# ADCs.net
KiCad netlist of a schematic drawn in Altium Designer
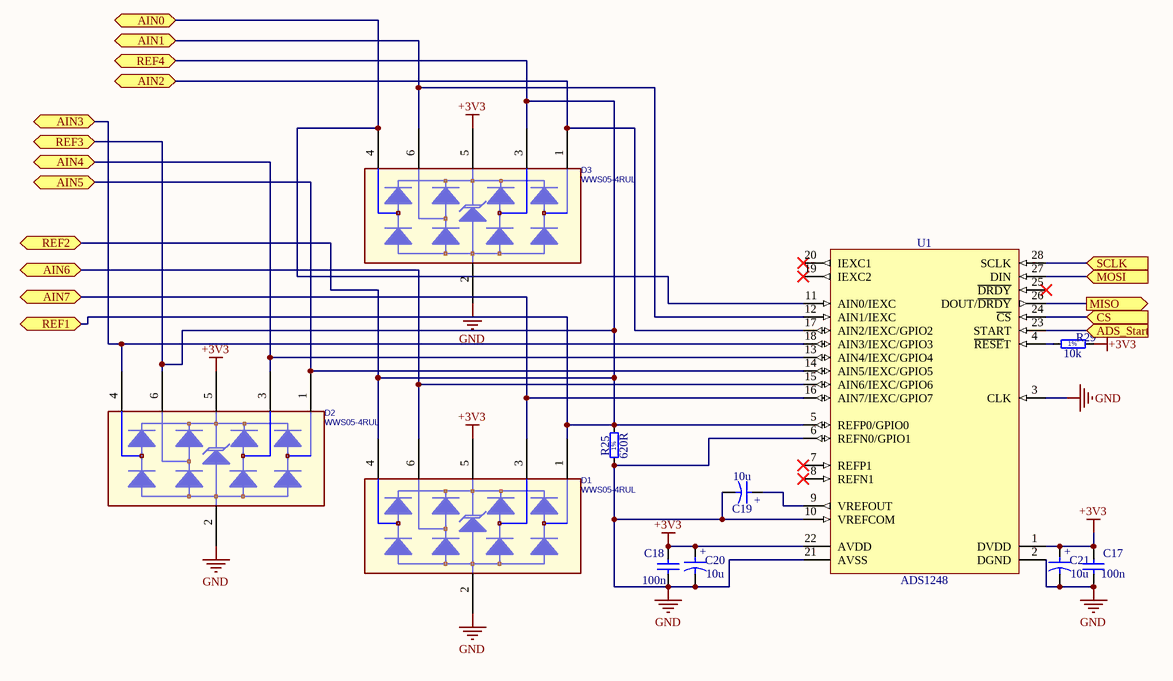
[diagram p0: ADCs.SchDoc]

(export (version "E")
  (design (tool "Eeschema 10.0.6"))
  (components
    (comp (ref "C17")
      (value "100n")
      (footprint "CAPC1005X55N")
      (description "Non-polarised capacitor")
      (fields
        (field (name "PART NUMBER") "CC0402_100NF_16V_10%_X7R")
        (field (name "VOLTAGE") "16V")
        (field (name "AUTHOR") "CERN DEM JLC")
      )
      (libsource (lib "Capacitors") (part "Capacitor - non polarized"))
    )
    (comp (ref "C18")
      (value "100n")
      (footprint "CAPC1005X55N")
      (description "Non-polarised capacitor")
      (fields
        (field (name "PART NUMBER") "CC0402_100NF_16V_10%_X7R")
        (field (name "VOLTAGE") "16V")
        (field (name "AUTHOR") "CERN DEM JLC")
      )
      (libsource (lib "Capacitors") (part "Capacitor - non polarized"))
    )
    (comp (ref "C19")
      (value "10u")
      (footprint "CAPMP3216X180N")
      (description "Polarised capacitor")
      (fields
        (field (name "PART NUMBER") "CTE7343-31_10UF_25V_10%")
        (field (name "VOLTAGE") "25V")
        (field (name "AUTHOR") "CERN DEM JMW")
      )
      (libsource (lib "Capacitors") (part "Capacitor - polarized"))
    )
    (comp (ref "C20")
      (value "10u")
      (footprint "CAPMP3216X180N")
      (description "Polarised capacitor")
      (fields
        (field (name "PART NUMBER") "CTE7343-31_10UF_25V_10%")
        (field (name "VOLTAGE") "25V")
        (field (name "AUTHOR") "CERN DEM JMW")
      )
      (libsource (lib "Capacitors") (part "Capacitor - polarized"))
    )
    (comp (ref "C21")
      (value "10u")
      (footprint "CAPMP3216X180N")
      (description "Polarised capacitor")
      (fields
        (field (name "PART NUMBER") "CTE7343-31_10UF_25V_10%")
        (field (name "VOLTAGE") "25V")
        (field (name "AUTHOR") "CERN DEM JMW")
      )
      (libsource (lib "Capacitors") (part "Capacitor - polarized"))
    )
    (comp (ref "D1")
      (value "WWS05-4RUL")
      (description "DIODE,RCLAMP0524P,SEMTECH")
      (libsource (lib "LIBRARY_SCH") (part "D_TVS_WWS05-4RUL"))
    )
    (comp (ref "D2")
      (value "WWS05-4RUL")
      (description "DIODE,RCLAMP0524P,SEMTECH")
      (libsource (lib "LIBRARY_SCH") (part "D_TVS_WWS05-4RUL"))
    )
    (comp (ref "D3")
      (value "WWS05-4RUL")
      (description "DIODE,RCLAMP0524P,SEMTECH")
      (libsource (lib "LIBRARY_SCH") (part "D_TVS_WWS05-4RUL"))
    )
    (comp (ref "R25")
      (value "620R")
      (footprint "RESC1005X40N")
      (description "Resistor - 1%")
      (fields
        (field (name "PART NUMBER") "R0402_620R_1%_0.0625W_100PPM")
        (field (name "POWER") "0.0625W")
        (field (name "AUTHOR") "CERN DEM JLC")
      )
      (libsource (lib "Resistors") (part "Resistor - 1%"))
    )
    (comp (ref "R29")
      (value "10k")
      (footprint "RESC1005X40N")
      (description "Resistor - 1%")
      (fields
        (field (name "PART NUMBER") "R0402_10K_1%_0.0625W_100PPM")
        (field (name "POWER") "0.0625W")
        (field (name "AUTHOR") "CERN DEM JLC")
      )
      (libsource (lib "Resistors") (part "Resistor - 1%"))
    )
    (comp (ref "U1")
      (value "ADS1248")
      (footprint "SOP65P640X120-28N")
      (description "24-Bit Analog-to-Digital Converter for Temperature Sensors")
      (fields
        (field (name "PART NUMBER") "ADS1248IPWR")
        (field (name "MANUFACTURER") "TEXAS INSTRUMENTS")
        (field (name "AUTHOR") "CERN DEM JLC")
      )
      (libsource (lib "ICs And Semiconductors") (part "ADS1248"))
    )
  )
  (nets
    (net (code "1") (name "+3V3") (class "Default")
      (node (ref "C17") (pin "2") (pinfunction "2_2") (pintype "passive"))
      (node (ref "C18") (pin "2") (pinfunction "2_2") (pintype "passive"))
      (node (ref "C20") (pin "1") (pinfunction "1_1") (pintype "passive"))
      (node (ref "C21") (pin "1") (pinfunction "1_1") (pintype "passive"))
      (node (ref "D1") (pin "5") (pinfunction "5_5") (pintype "passive"))
      (node (ref "D2") (pin "5") (pinfunction "5_5") (pintype "passive"))
      (node (ref "D3") (pin "5") (pinfunction "5_5") (pintype "passive"))
      (node (ref "R29") (pin "2") (pinfunction "2_2") (pintype "passive"))
      (node (ref "U1") (pin "1") (pinfunction "DVDD_1") (pintype "power_in"))
      (node (ref "U1") (pin "22") (pinfunction "AVDD_22") (pintype "power_in"))
    )
    (net (code "2") (name "/ADS_Start") (class "Default")
      (node (ref "U1") (pin "23") (pinfunction "START_23") (pintype "input"))
    )
    (net (code "3") (name "/AIN0") (class "Default")
      (node (ref "D3") (pin "4") (pinfunction "4_4") (pintype "passive"))
      (node (ref "U1") (pin "11") (pinfunction "AIN0/IEXC_11") (pintype "input"))
    )
    (net (code "4") (name "/AIN1") (class "Default")
      (node (ref "D3") (pin "6") (pinfunction "6_6") (pintype "passive"))
      (node (ref "U1") (pin "12") (pinfunction "AIN1/IEXC_12") (pintype "input"))
    )
    (net (code "5") (name "/AIN2") (class "Default")
      (node (ref "D3") (pin "1") (pinfunction "1_1") (pintype "passive"))
      (node (ref "U1") (pin "17") (pinfunction "AIN2/IEXC/GPIO2_17") (pintype "bidirectional"))
    )
    (net (code "6") (name "/AIN3") (class "Default")
      (node (ref "D2") (pin "4") (pinfunction "4_4") (pintype "passive"))
      (node (ref "U1") (pin "18") (pinfunction "AIN3/IEXC/GPIO3_18") (pintype "bidirectional"))
    )
    (net (code "7") (name "/AIN4") (class "Default")
      (node (ref "D2") (pin "3") (pinfunction "3_3") (pintype "passive"))
      (node (ref "U1") (pin "13") (pinfunction "AIN4/IEXC/GPIO4_13") (pintype "bidirectional"))
    )
    (net (code "8") (name "/AIN5") (class "Default")
      (node (ref "D2") (pin "1") (pinfunction "1_1") (pintype "passive"))
      (node (ref "U1") (pin "14") (pinfunction "AIN5/IEXC/GPIO5_14") (pintype "bidirectional"))
    )
    (net (code "9") (name "/AIN6") (class "Default")
      (node (ref "D1") (pin "6") (pinfunction "6_6") (pintype "passive"))
      (node (ref "U1") (pin "15") (pinfunction "AIN6/IEXC/GPIO6_15") (pintype "bidirectional"))
    )
    (net (code "10") (name "/AIN7") (class "Default")
      (node (ref "D1") (pin "3") (pinfunction "3_3") (pintype "passive"))
      (node (ref "U1") (pin "16") (pinfunction "AIN7/IEXC/GPIO7_16") (pintype "bidirectional"))
    )
    (net (code "11") (name "/CS") (class "Default")
      (node (ref "U1") (pin "24") (pinfunction "~{CS}_24") (pintype "input"))
    )
    (net (code "12") (name "/MISO") (class "Default")
      (node (ref "U1") (pin "26") (pinfunction "DOUT/~{DRDY}_26") (pintype "output"))
    )
    (net (code "13") (name "/MOSI") (class "Default")
      (node (ref "U1") (pin "27") (pinfunction "DIN_27") (pintype "input"))
    )
    (net (code "14") (name "/REF1") (class "Default")
      (node (ref "D1") (pin "1") (pinfunction "1_1") (pintype "passive"))
      (node (ref "D1") (pin "4") (pinfunction "4_4") (pintype "passive"))
      (node (ref "D2") (pin "6") (pinfunction "6_6") (pintype "passive"))
      (node (ref "D3") (pin "3") (pinfunction "3_3") (pintype "passive"))
      (node (ref "R25") (pin "2") (pinfunction "2_2") (pintype "passive"))
      (node (ref "U1") (pin "5") (pinfunction "REFP0/GPIO0_5") (pintype "bidirectional"))
    )
    (net (code "15") (name "/SCLK") (class "Default")
      (node (ref "U1") (pin "28") (pinfunction "SCLK_28") (pintype "input"))
    )
    (net (code "16") (name "GND") (class "Default")
      (node (ref "C17") (pin "1") (pinfunction "1_1") (pintype "passive"))
      (node (ref "C18") (pin "1") (pinfunction "1_1") (pintype "passive"))
      (node (ref "C19") (pin "2") (pinfunction "2_2") (pintype "passive"))
      (node (ref "C20") (pin "2") (pinfunction "2_2") (pintype "passive"))
      (node (ref "C21") (pin "2") (pinfunction "2_2") (pintype "passive"))
      (node (ref "D1") (pin "2") (pinfunction "2_2") (pintype "passive"))
      (node (ref "D2") (pin "2") (pinfunction "2_2") (pintype "passive"))
      (node (ref "D3") (pin "2") (pinfunction "2_2") (pintype "passive"))
      (node (ref "R25") (pin "1") (pinfunction "1_1") (pintype "passive"))
      (node (ref "U1") (pin "10") (pinfunction "VREFCOM_10") (pintype "input"))
      (node (ref "U1") (pin "2") (pinfunction "DGND_2") (pintype "power_in"))
      (node (ref "U1") (pin "21") (pinfunction "AVSS_21") (pintype "power_in"))
      (node (ref "U1") (pin "3") (pinfunction "CLK_3") (pintype "input"))
      (node (ref "U1") (pin "6") (pinfunction "REFN0/GPIO1_6") (pintype "bidirectional"))
    )
    (net (code "17") (name "Net-(U1-VREFOUT)") (class "Default")
      (node (ref "C19") (pin "1") (pinfunction "1_1") (pintype "passive"))
      (node (ref "U1") (pin "9") (pinfunction "VREFOUT_9") (pintype "output"))
    )
    (net (code "18") (name "Net-(U1-~{RESE}T)") (class "Default")
      (node (ref "R29") (pin "1") (pinfunction "1_1") (pintype "passive"))
      (node (ref "U1") (pin "4") (pinfunction "~{RESE}T_4") (pintype "input"))
    )
    (net (code "19") (name "unconnected-(U1-IEXC1-Pad20)") (class "Default")
      (node (ref "U1") (pin "20") (pinfunction "IEXC1_20") (pintype "output+no_connect"))
    )
    (net (code "20") (name "unconnected-(U1-IEXC2-Pad19)") (class "Default")
      (node (ref "U1") (pin "19") (pinfunction "IEXC2_19") (pintype "output+no_connect"))
    )
    (net (code "21") (name "unconnected-(U1-REFN1-Pad8)") (class "Default")
      (node (ref "U1") (pin "8") (pinfunction "REFN1_8") (pintype "input+no_connect"))
    )
    (net (code "22") (name "unconnected-(U1-REFP1-Pad7)") (class "Default")
      (node (ref "U1") (pin "7") (pinfunction "REFP1_7") (pintype "input+no_connect"))
    )
    (net (code "23") (name "unconnected-(U1-~{DRDY}-Pad25)") (class "Default")
      (node (ref "U1") (pin "25") (pinfunction "~{DRDY}_25") (pintype "input+no_connect"))
    )
  )
)
